# Net.net
KiCad netlist of a schematic drawn in Altium Designer
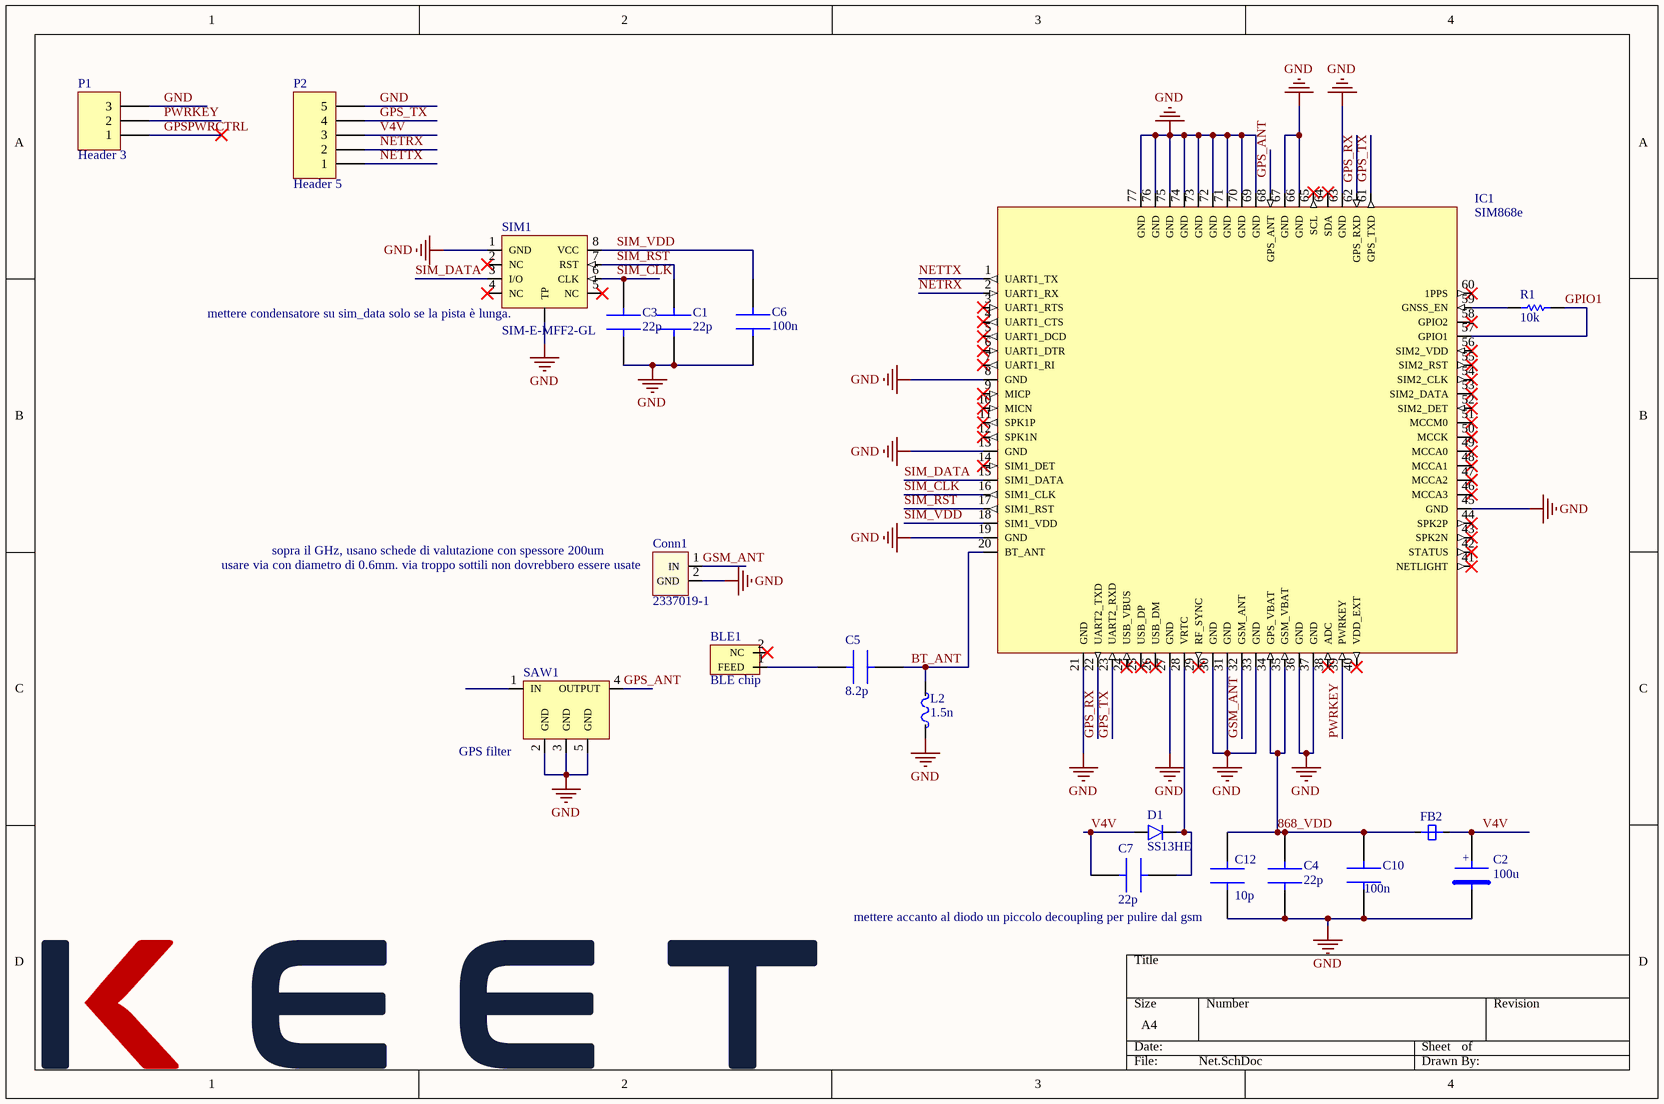
[diagram p0: Net.SchDoc]

(export (version "E")
  (design (tool "Eeschema 10.0.6"))
  (components
    (comp (ref "BLE1")
      (value "BLE chip")
      (footprint "BLE antenna")
      (description "RF ANT 2.4GHZ CHIP SOLDER SMD")
      (fields
        (field (name "MANUFACTURER") "Johanson")
        (field (name "MANUFACTURER PART NUMBER") "2450AT14A0100T")
      )
      (libsource (lib "KeetV2") (part "2450AT14A0100T"))
    )
    (comp (ref "C1")
      (value "22p")
      (footprint "CAPC1005X06N")
      (description "CAP CER 22PF 50V C0G/NP0 0402")
      (fields
        (field (name "MANUFACTURER") "Kyocera AVX")
        (field (name "MANUFACTURER PART NUMBER") "04025A220GAT2A")
      )
      (libsource (lib "KeetV2") (part "04025A220GAT2A"))
    )
    (comp (ref "C2")
      (value "100u")
      (footprint "CAPMP3528X21N")
      (description "Capacitor; Tantalum; Cap 100 uF; Tol 10%; Vol-Rtg 6.3 VDC; SMT; 3528; ESR 250 mOhms; CT")
      (fields
        (field (name "MANUFACTURER") "Kyocera AVX")
        (field (name "MANUFACTURER PART NUMBER") "TPSB107K006R0250")
      )
      (libsource (lib "KeetV2") (part "TPSB107K006R0250"))
    )
    (comp (ref "C3")
      (value "22p")
      (footprint "CAPC1005X06N")
      (description "CAP CER 22PF 50V C0G/NP0 0402")
      (fields
        (field (name "MANUFACTURER") "Kyocera AVX")
        (field (name "MANUFACTURER PART NUMBER") "04025A220GAT2A")
      )
      (libsource (lib "KeetV2") (part "04025A220GAT2A"))
    )
    (comp (ref "C4")
      (value "22p")
      (footprint "CAPC1005X06N")
      (description "CAP CER 22PF 50V C0G/NP0 0402")
      (fields
        (field (name "MANUFACTURER") "Kyocera AVX")
        (field (name "MANUFACTURER PART NUMBER") "04025A220GAT2A")
      )
      (libsource (lib "KeetV2") (part "04025A220GAT2A"))
    )
    (comp (ref "C5")
      (value "8.2p")
      (footprint "CAPC1005X06N")
      (description "0402 8.2 pF 50V ±0.25 pF Tolerance C0G SMT Multilayer Ceramic Capacitor")
      (fields
        (field (name "MANUFACTURER") "Murata")
        (field (name "MANUFACTURER PART NUMBER") "GJM1555C1H8R2CB01D")
      )
      (libsource (lib "KeetV2") (part "GJM1555C1H8R2CB01D"))
    )
    (comp (ref "C6")
      (value "100n")
      (footprint "CAPC1005X06N")
      (description "CAP CER 0.1UF 16V X7R 0402")
      (fields
        (field (name "MANUFACTURER") "Murata")
        (field (name "MANUFACTURER PART NUMBER") "GRM155R71C104KA88D")
      )
      (libsource (lib "KeetV2") (part "GRM155R71C104KA88D"))
    )
    (comp (ref "C7")
      (value "22p")
      (footprint "CAPC1005X06N")
      (description "CAP CER 22PF 50V C0G/NP0 0402")
      (fields
        (field (name "MANUFACTURER") "Kyocera AVX")
        (field (name "MANUFACTURER PART NUMBER") "04025A220GAT2A")
      )
      (libsource (lib "KeetV2") (part "04025A220GAT2A"))
    )
    (comp (ref "C10")
      (value "100n")
      (footprint "CAPC1005X06N")
      (description "CAP CER 0.1UF 16V X7R 0402")
      (fields
        (field (name "MANUFACTURER") "Murata")
        (field (name "MANUFACTURER PART NUMBER") "GRM155R71C104KA88D")
      )
      (libsource (lib "KeetV2") (part "GRM155R71C104KA88D"))
    )
    (comp (ref "C12")
      (value "10p")
      (footprint "CAPC1005X06N")
      (description "Multilayer Ceramic Capacitors MLCC - SMD/SMT 25V 10pF ThnFlm 0402 1% Tol")
      (fields
        (field (name "MANUFACTURER") "Kyocera AVX")
        (field (name "MANUFACTURER PART NUMBER") "04023J100FBSTR")
      )
      (libsource (lib "KeetV2") (part "04023J100FBSTR"))
    )
    (comp (ref "Conn1")
      (value "2337019-1")
      (footprint "IPEX_CONNECTOR_RF")
      (description "RF Connector; Coaxial Connectors MicroCoax receptacle UMCC Gen 1")
      (fields (field (name "MANUFACTURER") "TE Connectivity"))
      (libsource (lib "KeetV2") (part "2337019-1"))
    )
    (comp (ref "D1")
      (value "SS13HE")
      (footprint "SODFL250X75-2N")
      (description "SS13HE Series 30 V 1 A Surface Mount Schottky Barrier Rectifier - SOD-323HE")
      (fields (field (name "MANUFACTURER") "ON Semiconductor / Fairchild"))
      (libsource (lib "KeetV2") (part "SS13HE"))
    )
    (comp (ref "FB2")
      (value "FBMH2012HM221-T")
      (footprint "INDC2012X14N")
      (description "Ferrite Beads HI CUR CHIP BD 0805 220OHMS 25%")
      (fields (field (name "MANUFACTURER") "Taiyo Yuden") (field (name "TOLERANCE") "25%"))
      (libsource (lib "KeetV2") (part "FBMH2012HM221-T"))
    )
    (comp (ref "IC1")
      (value "SIM868e")
      (footprint "SIM868e")
      (description "Sim 828e")
      (libsource (lib "KeetV2") (part "SIM868e"))
    )
    (comp (ref "L2")
      (value "1.5n")
      (footprint "INDC1005X06N")
      (description "FIXED IND 1.5NH 1A 100 MOHM")
      (fields
        (field (name "MANUFACTURER") "Murata")
        (field (name "MANUFACTURER PART NUMBER") "LQG15HN1N5S02D")
      )
      (libsource (lib "KeetV2") (part "LQG15HN1N5S02D"))
    )
    (comp (ref "P1")
      (value "Header 3")
      (footprint "HDR1X3")
      (description "Header, 3-Pin")
      (fields (field (name "PUBLISHER") "Altium Limited"))
      (libsource (lib "Miscellaneous Connectors") (part "Header 3"))
    )
    (comp (ref "P2")
      (value "Header 5")
      (footprint "HDR1X5")
      (description "Header, 5-Pin")
      (fields (field (name "PUBLISHER") "Altium Limited"))
      (libsource (lib "Miscellaneous Connectors") (part "Header 5"))
    )
    (comp (ref "R1")
      (value "10k")
      (footprint "RESC1005X04N")
      (fields
        (field (name "MANUFACTURER") "Panasonic")
        (field (name "MANUFACTURER PART NUMBER") "ERJ-U02F1002X")
        (field (name "TOLERANCE") "1%")
      )
      (libsource (lib "KeetV2") (part "ERJ-U02F1002X"))
    )
    (comp (ref "SAW1")
      (value "GPS filter")
      (footprint "SAW")
      (description "Signal Conditioning SAW FILTER 1582MHz")
      (fields
        (field (name "MANUFACTURER") "Kyocera AVX")
        (field (name "MANUFACTURER PART NUMBER") "SF14-1582M5UUD2")
      )
      (libsource (lib "KeetV2") (part "SF14-1582M5UUD2"))
    )
    (comp (ref "SIM1")
      (value "SIM-E-MFF2-GL")
      (footprint "MFF2 SIM")
      (fields (field (name "MANUFACTURER") "Hologram"))
      (libsource (lib "KeetV2") (part "SIM-E-MFF2-GL"))
    )
  )
  (nets
    (net (code "1") (name "/868_VDD") (class "Default")
      (node (ref "C10") (pin "1") (pinfunction "1_1") (pintype "passive"))
      (node (ref "C12") (pin "2") (pinfunction "2_2") (pintype "passive"))
      (node (ref "C4") (pin "2") (pinfunction "2_2") (pintype "passive"))
      (node (ref "FB2") (pin "1") (pinfunction "1_1") (pintype "passive"))
      (node (ref "IC1") (pin "34") (pinfunction "GPS_VBAT_34") (pintype "input"))
      (node (ref "IC1") (pin "35") (pinfunction "GSM_VBAT_35") (pintype "input"))
    )
    (net (code "2") (name "/BT_ANT") (class "Default")
      (node (ref "C5") (pin "2") (pinfunction "2_2") (pintype "passive"))
      (node (ref "IC1") (pin "20") (pinfunction "BT_ANT_20") (pintype "bidirectional"))
      (node (ref "L2") (pin "2") (pinfunction "2_2") (pintype "passive"))
    )
    (net (code "3") (name "/GPIO1") (class "Default")
      (node (ref "IC1") (pin "57") (pinfunction "GPIO1_57") (pintype "bidirectional"))
      (node (ref "R1") (pin "2") (pinfunction "2_2") (pintype "passive"))
    )
    (net (code "4") (name "/GPSPWRCTRL") (class "Default")
      (node (ref "P1") (pin "1") (pinfunction "1_1") (pintype "passive+no_connect"))
    )
    (net (code "5") (name "/GPS_ANT") (class "Default")
      (node (ref "IC1") (pin "68") (pinfunction "GPS_ANT_68") (pintype "input"))
      (node (ref "SAW1") (pin "4") (pinfunction "OUTPUT_4") (pintype "passive"))
    )
    (net (code "6") (name "/GPS_RX") (class "Default")
      (node (ref "IC1") (pin "22") (pinfunction "UART2_TXD_22") (pintype "output"))
      (node (ref "IC1") (pin "62") (pinfunction "GPS_RXD_62") (pintype "input"))
    )
    (net (code "7") (name "/GPS_TX") (class "Default")
      (node (ref "IC1") (pin "23") (pinfunction "UART2_RXD_23") (pintype "input"))
      (node (ref "IC1") (pin "61") (pinfunction "GPS_TXD_61") (pintype "output"))
      (node (ref "P2") (pin "4") (pinfunction "4_4") (pintype "passive"))
    )
    (net (code "8") (name "/GSM_ANT") (class "Default")
      (node (ref "Conn1") (pin "1") (pinfunction "IN_1") (pintype "bidirectional"))
      (node (ref "IC1") (pin "32") (pinfunction "GSM_ANT_32") (pintype "bidirectional"))
    )
    (net (code "9") (name "/NETRX") (class "Default")
      (node (ref "IC1") (pin "2") (pinfunction "UART1_RX_2") (pintype "input"))
      (node (ref "P2") (pin "2") (pinfunction "2_2") (pintype "passive"))
    )
    (net (code "10") (name "/NETTX") (class "Default")
      (node (ref "IC1") (pin "1") (pinfunction "UART1_TX_1") (pintype "output"))
      (node (ref "P2") (pin "1") (pinfunction "1_1") (pintype "passive"))
    )
    (net (code "11") (name "/PWRKEY") (class "Default")
      (node (ref "IC1") (pin "39") (pinfunction "PWRKEY_39") (pintype "input"))
      (node (ref "P1") (pin "2") (pinfunction "2_2") (pintype "passive"))
    )
    (net (code "12") (name "/SIM_CLK") (class "Default")
      (node (ref "C3") (pin "2") (pinfunction "2_2") (pintype "passive"))
      (node (ref "IC1") (pin "16") (pinfunction "SIM1_CLK_16") (pintype "output"))
      (node (ref "SIM1") (pin "6") (pinfunction "CLK_6") (pintype "input"))
    )
    (net (code "13") (name "/SIM_DATA") (class "Default")
      (node (ref "IC1") (pin "15") (pinfunction "SIM1_DATA_15") (pintype "bidirectional"))
      (node (ref "SIM1") (pin "3") (pinfunction "I/O_3") (pintype "bidirectional"))
    )
    (net (code "14") (name "/SIM_RST") (class "Default")
      (node (ref "C1") (pin "2") (pinfunction "2_2") (pintype "passive"))
      (node (ref "IC1") (pin "17") (pinfunction "SIM1_RST_17") (pintype "output"))
      (node (ref "SIM1") (pin "7") (pinfunction "RST_7") (pintype "input"))
    )
    (net (code "15") (name "/SIM_VDD") (class "Default")
      (node (ref "C6") (pin "1") (pinfunction "1_1") (pintype "passive"))
      (node (ref "IC1") (pin "18") (pinfunction "SIM1_VDD_18") (pintype "passive"))
      (node (ref "SIM1") (pin "8") (pinfunction "VCC_8") (pintype "power_in"))
    )
    (net (code "16") (name "/V4V") (class "Default")
      (node (ref "C2") (pin "1") (pinfunction "1_1") (pintype "passive"))
      (node (ref "C7") (pin "1") (pinfunction "1_1") (pintype "passive"))
      (node (ref "D1") (pin "1") (pinfunction "A_1") (pintype "passive"))
      (node (ref "FB2") (pin "2") (pinfunction "2_2") (pintype "passive"))
      (node (ref "P2") (pin "3") (pinfunction "3_3") (pintype "passive"))
    )
    (net (code "17") (name "GND") (class "Default")
      (node (ref "C1") (pin "1") (pinfunction "1_1") (pintype "passive"))
      (node (ref "C10") (pin "2") (pinfunction "2_2") (pintype "passive"))
      (node (ref "C12") (pin "1") (pinfunction "1_1") (pintype "passive"))
      (node (ref "C2") (pin "2") (pinfunction "2_2") (pintype "passive"))
      (node (ref "C3") (pin "1") (pinfunction "1_1") (pintype "passive"))
      (node (ref "C4") (pin "1") (pinfunction "1_1") (pintype "passive"))
      (node (ref "C6") (pin "2") (pinfunction "2_2") (pintype "passive"))
      (node (ref "Conn1") (pin "2") (pinfunction "GND_2") (pintype "passive"))
      (node (ref "IC1") (pin "13") (pinfunction "GND_13") (pintype "power_in"))
      (node (ref "IC1") (pin "19") (pinfunction "GND_19") (pintype "power_in"))
      (node (ref "IC1") (pin "21") (pinfunction "GND_21") (pintype "power_in"))
      (node (ref "IC1") (pin "27") (pinfunction "GND_27") (pintype "power_in"))
      (node (ref "IC1") (pin "30") (pinfunction "GND_30") (pintype "power_in"))
      (node (ref "IC1") (pin "31") (pinfunction "GND_31") (pintype "power_in"))
      (node (ref "IC1") (pin "33") (pinfunction "GND_33") (pintype "power_in"))
      (node (ref "IC1") (pin "36") (pinfunction "GND_36") (pintype "power_in"))
      (node (ref "IC1") (pin "37") (pinfunction "GND_37") (pintype "power_in"))
      (node (ref "IC1") (pin "45") (pinfunction "GND_45") (pintype "power_in"))
      (node (ref "IC1") (pin "63") (pinfunction "GND_63") (pintype "power_in"))
      (node (ref "IC1") (pin "66") (pinfunction "GND_66") (pintype "power_in"))
      (node (ref "IC1") (pin "67") (pinfunction "GND_67") (pintype "power_in"))
      (node (ref "IC1") (pin "69") (pinfunction "GND_69") (pintype "power_in"))
      (node (ref "IC1") (pin "70") (pinfunction "GND_70") (pintype "power_in"))
      (node (ref "IC1") (pin "71") (pinfunction "GND_71") (pintype "power_in"))
      (node (ref "IC1") (pin "72") (pinfunction "GND_72") (pintype "power_in"))
      (node (ref "IC1") (pin "73") (pinfunction "GND_73") (pintype "power_in"))
      (node (ref "IC1") (pin "74") (pinfunction "GND_74") (pintype "power_in"))
      (node (ref "IC1") (pin "75") (pinfunction "GND_75") (pintype "power_in"))
      (node (ref "IC1") (pin "76") (pinfunction "GND_76") (pintype "power_in"))
      (node (ref "IC1") (pin "77") (pinfunction "GND_77") (pintype "power_in"))
      (node (ref "IC1") (pin "8") (pinfunction "GND_8") (pintype "power_in"))
      (node (ref "L2") (pin "1") (pinfunction "1_1") (pintype "passive"))
      (node (ref "P1") (pin "3") (pinfunction "3_3") (pintype "passive"))
      (node (ref "P2") (pin "5") (pinfunction "5_5") (pintype "passive"))
      (node (ref "SAW1") (pin "2") (pinfunction "GND_2") (pintype "passive"))
      (node (ref "SAW1") (pin "3") (pinfunction "GND_3") (pintype "passive"))
      (node (ref "SAW1") (pin "5") (pinfunction "GND_5") (pintype "passive"))
      (node (ref "SIM1") (pin "1") (pinfunction "GND_1") (pintype "power_in"))
      (node (ref "SIM1") (pin "9") (pinfunction "TP_9") (pintype "passive"))
    )
    (net (code "18") (name "Net-(BLE1-FEED)") (class "Default")
      (node (ref "BLE1") (pin "1") (pinfunction "FEED_1") (pintype "passive"))
      (node (ref "C5") (pin "1") (pinfunction "1_1") (pintype "passive"))
    )
    (net (code "19") (name "Net-(D1-K)") (class "Default")
      (node (ref "C7") (pin "2") (pinfunction "2_2") (pintype "passive"))
      (node (ref "D1") (pin "2") (pinfunction "K_2") (pintype "passive"))
      (node (ref "IC1") (pin "28") (pinfunction "VRTC_28") (pintype "bidirectional"))
    )
    (net (code "20") (name "Net-(IC1-GNSS_EN)") (class "Default")
      (node (ref "IC1") (pin "59") (pinfunction "GNSS_EN_59") (pintype "input"))
      (node (ref "R1") (pin "1") (pinfunction "1_1") (pintype "passive"))
    )
    (net (code "21") (name "unconnected-(BLE1-NC-Pad2)") (class "Default")
      (node (ref "BLE1") (pin "2") (pinfunction "NC_2") (pintype "passive+no_connect"))
    )
    (net (code "22") (name "unconnected-(IC1-1PPS-Pad60)") (class "Default")
      (node (ref "IC1") (pin "60") (pinfunction "1PPS_60") (pintype "output+no_connect"))
    )
    (net (code "23") (name "unconnected-(IC1-ADC-Pad38)") (class "Default")
      (node (ref "IC1") (pin "38") (pinfunction "ADC_38") (pintype "input+no_connect"))
    )
    (net (code "24") (name "unconnected-(IC1-GPIO2-Pad58)") (class "Default")
      (node (ref "IC1") (pin "58") (pinfunction "GPIO2_58") (pintype "bidirectional+no_connect"))
    )
    (net (code "25") (name "unconnected-(IC1-MCCA0-Pad49)") (class "Default")
      (node (ref "IC1") (pin "49") (pinfunction "MCCA0_49") (pintype "bidirectional+no_connect"))
    )
    (net (code "26") (name "unconnected-(IC1-MCCA1-Pad48)") (class "Default")
      (node (ref "IC1") (pin "48") (pinfunction "MCCA1_48") (pintype "bidirectional+no_connect"))
    )
    (net (code "27") (name "unconnected-(IC1-MCCA2-Pad47)") (class "Default")
      (node (ref "IC1") (pin "47") (pinfunction "MCCA2_47") (pintype "bidirectional+no_connect"))
    )
    (net (code "28") (name "unconnected-(IC1-MCCA3-Pad46)") (class "Default")
      (node (ref "IC1") (pin "46") (pinfunction "MCCA3_46") (pintype "bidirectional+no_connect"))
    )
    (net (code "29") (name "unconnected-(IC1-MCCK-Pad50)") (class "Default")
      (node (ref "IC1") (pin "50") (pinfunction "MCCK_50") (pintype "bidirectional+no_connect"))
    )
    (net (code "30") (name "unconnected-(IC1-MCCM0-Pad51)") (class "Default")
      (node (ref "IC1") (pin "51") (pinfunction "MCCM0_51") (pintype "bidirectional+no_connect"))
    )
    (net (code "31") (name "unconnected-(IC1-MICN-Pad10)") (class "Default")
      (node (ref "IC1") (pin "10") (pinfunction "MICN_10") (pintype "input+no_connect"))
    )
    (net (code "32") (name "unconnected-(IC1-MICP-Pad9)") (class "Default")
      (node (ref "IC1") (pin "9") (pinfunction "MICP_9") (pintype "input+no_connect"))
    )
    (net (code "33") (name "unconnected-(IC1-NETLIGHT-Pad41)") (class "Default")
      (node (ref "IC1") (pin "41") (pinfunction "NETLIGHT_41") (pintype "output+no_connect"))
    )
    (net (code "34") (name "unconnected-(IC1-RF_SYNC-Pad29)") (class "Default")
      (node (ref "IC1") (pin "29") (pinfunction "RF_SYNC_29") (pintype "output+no_connect"))
    )
    (net (code "35") (name "unconnected-(IC1-SCL-Pad65)") (class "Default")
      (node (ref "IC1") (pin "65") (pinfunction "SCL_65") (pintype "output+no_connect"))
    )
    (net (code "36") (name "unconnected-(IC1-SDA-Pad64)") (class "Default")
      (node (ref "IC1") (pin "64") (pinfunction "SDA_64") (pintype "bidirectional+no_connect"))
    )
    (net (code "37") (name "unconnected-(IC1-SIM1_DET-Pad14)") (class "Default")
      (node (ref "IC1") (pin "14") (pinfunction "SIM1_DET_14") (pintype "input+no_connect"))
    )
    (net (code "38") (name "unconnected-(IC1-SIM2_CLK-Pad54)") (class "Default")
      (node (ref "IC1") (pin "54") (pinfunction "SIM2_CLK_54") (pintype "output+no_connect"))
    )
    (net (code "39") (name "unconnected-(IC1-SIM2_DATA-Pad53)") (class "Default")
      (node (ref "IC1") (pin "53") (pinfunction "SIM2_DATA_53") (pintype "bidirectional+no_connect"))
    )
    (net (code "40") (name "unconnected-(IC1-SIM2_DET-Pad52)") (class "Default")
      (node (ref "IC1") (pin "52") (pinfunction "SIM2_DET_52") (pintype "input+no_connect"))
    )
    (net (code "41") (name "unconnected-(IC1-SIM2_RST-Pad55)") (class "Default")
      (node (ref "IC1") (pin "55") (pinfunction "SIM2_RST_55") (pintype "output+no_connect"))
    )
    (net (code "42") (name "unconnected-(IC1-SIM2_VDD-Pad56)") (class "Default")
      (node (ref "IC1") (pin "56") (pinfunction "SIM2_VDD_56") (pintype "input+no_connect"))
    )
    (net (code "43") (name "unconnected-(IC1-SPK1N-Pad12)") (class "Default")
      (node (ref "IC1") (pin "12") (pinfunction "SPK1N_12") (pintype "output+no_connect"))
    )
    (net (code "44") (name "unconnected-(IC1-SPK1P-Pad11)") (class "Default")
      (node (ref "IC1") (pin "11") (pinfunction "SPK1P_11") (pintype "output+no_connect"))
    )
    (net (code "45") (name "unconnected-(IC1-SPK2N-Pad43)") (class "Default")
      (node (ref "IC1") (pin "43") (pinfunction "SPK2N_43") (pintype "output+no_connect"))
    )
    (net (code "46") (name "unconnected-(IC1-SPK2P-Pad44)") (class "Default")
      (node (ref "IC1") (pin "44") (pinfunction "SPK2P_44") (pintype "output+no_connect"))
    )
    (net (code "47") (name "unconnected-(IC1-STATUS-Pad42)") (class "Default")
      (node (ref "IC1") (pin "42") (pinfunction "STATUS_42") (pintype "output+no_connect"))
    )
    (net (code "48") (name "unconnected-(IC1-UART1_CTS-Pad4)") (class "Default")
      (node (ref "IC1") (pin "4") (pinfunction "UART1_CTS_4") (pintype "output+no_connect"))
    )
    (net (code "49") (name "unconnected-(IC1-UART1_DCD-Pad5)") (class "Default")
      (node (ref "IC1") (pin "5") (pinfunction "UART1_DCD_5") (pintype "output+no_connect"))
    )
    (net (code "50") (name "unconnected-(IC1-UART1_DTR-Pad6)") (class "Default")
      (node (ref "IC1") (pin "6") (pinfunction "UART1_DTR_6") (pintype "input+no_connect"))
    )
    (net (code "51") (name "unconnected-(IC1-UART1_RI-Pad7)") (class "Default")
      (node (ref "IC1") (pin "7") (pinfunction "UART1_RI_7") (pintype "output+no_connect"))
    )
    (net (code "52") (name "unconnected-(IC1-UART1_RTS-Pad3)") (class "Default")
      (node (ref "IC1") (pin "3") (pinfunction "UART1_RTS_3") (pintype "input+no_connect"))
    )
    (net (code "53") (name "unconnected-(IC1-USB_DM-Pad26)") (class "Default")
      (node (ref "IC1") (pin "26") (pinfunction "USB_DM_26") (pintype "bidirectional+no_connect"))
    )
    (net (code "54") (name "unconnected-(IC1-USB_DP-Pad25)") (class "Default")
      (node (ref "IC1") (pin "25") (pinfunction "USB_DP_25") (pintype "bidirectional+no_connect"))
    )
    (net (code "55") (name "unconnected-(IC1-USB_VBUS-Pad24)") (class "Default")
      (node (ref "IC1") (pin "24") (pinfunction "USB_VBUS_24") (pintype "input+no_connect"))
    )
    (net (code "56") (name "unconnected-(IC1-VDD_EXT-Pad40)") (class "Default")
      (node (ref "IC1") (pin "40") (pinfunction "VDD_EXT_40") (pintype "output+no_connect"))
    )
    (net (code "57") (name "unconnected-(SAW1-IN-Pad1)") (class "Default")
      (node (ref "SAW1") (pin "1") (pinfunction "IN_1") (pintype "passive"))
    )
    (net (code "58") (name "unconnected-(SIM1-NC-Pad2)") (class "Default")
      (node (ref "SIM1") (pin "2") (pinfunction "NC_2") (pintype "passive+no_connect"))
    )
    (net (code "59") (name "unconnected-(SIM1-NC-Pad4)") (class "Default")
      (node (ref "SIM1") (pin "4") (pinfunction "NC_4") (pintype "passive+no_connect"))
    )
    (net (code "60") (name "unconnected-(SIM1-NC-Pad5)") (class "Default")
      (node (ref "SIM1") (pin "5") (pinfunction "NC_5") (pintype "passive+no_connect"))
    )
  )
)
